# EGB220.net
KiCad netlist of a schematic drawn in Altium Designer
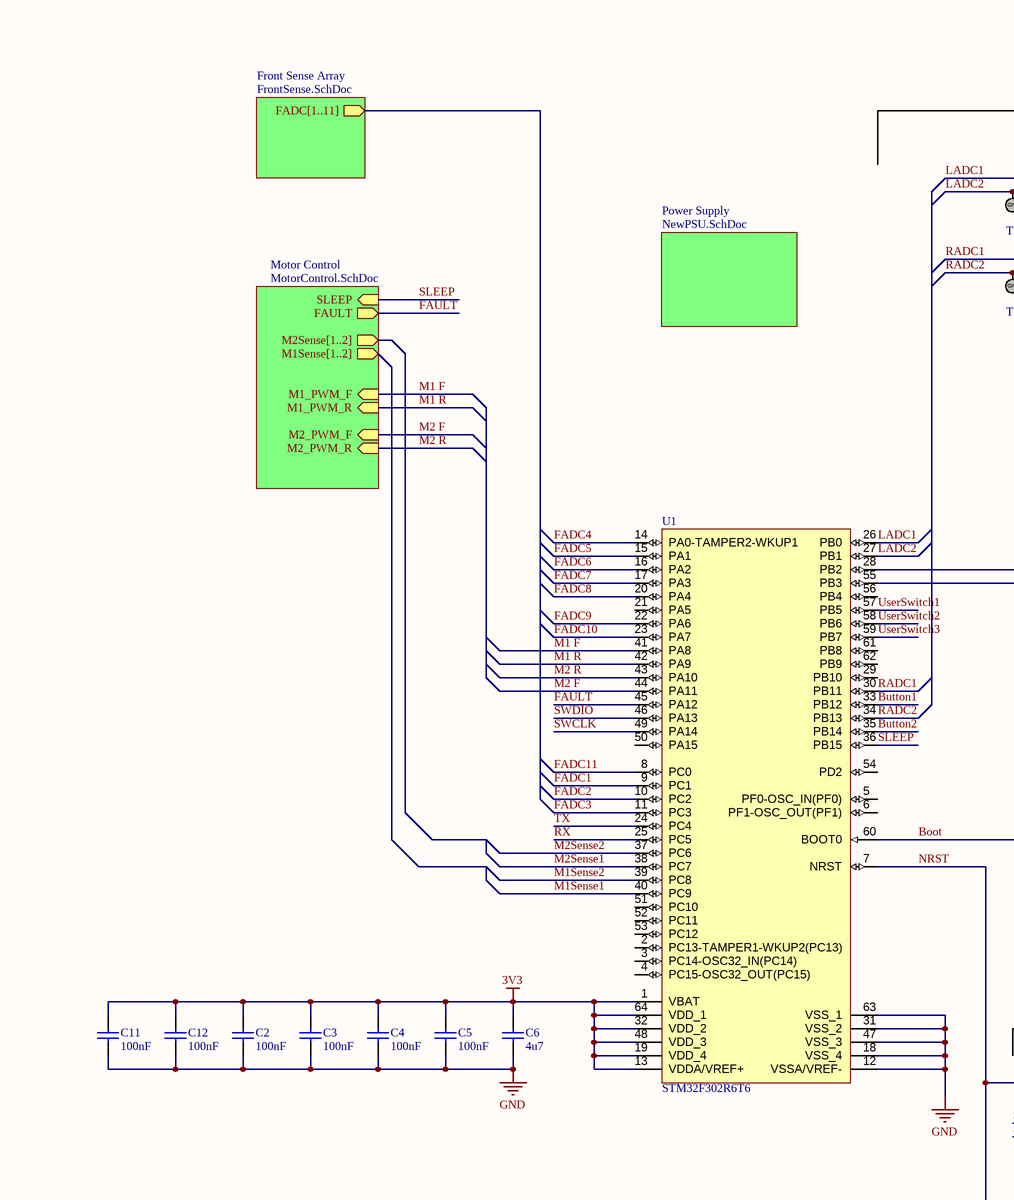
[diagram p0: EGB220.SchDoc, centre column 2 of 4]
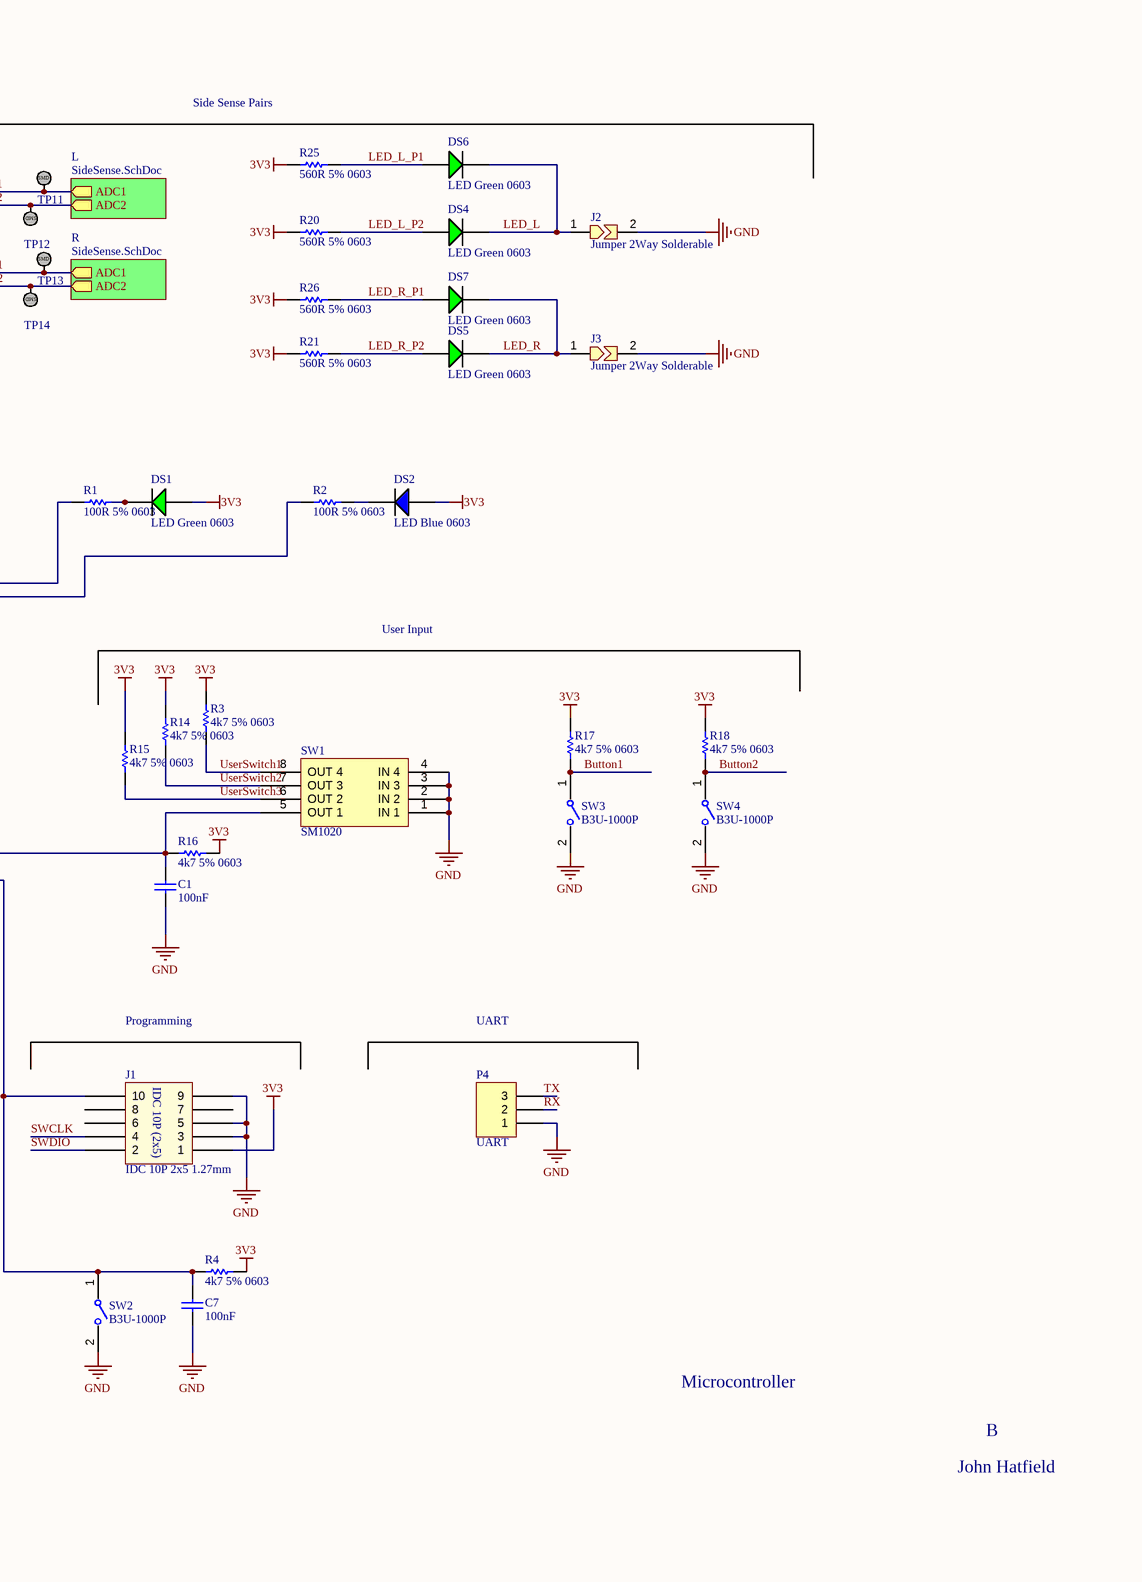
[diagram p1: EGB220.SchDoc, centre column 3 of 4]

(export (version "E")
  (design (tool "Eeschema 10.0.6"))
  (components
    (comp (ref "C1")
      (value "100nF")
      (footprint "Cap_Ceramic_0603")
      (description "Capacitor, Ceramic, SMD, 100nF, 50V, 5%, X7R, 0603")
      (libsource (lib "StandardCapacitors") (part "100nF 50V 5% X7R 0603"))
    )
    (comp (ref "C2")
      (value "100nF")
      (footprint "Cap_Ceramic_0603")
      (description "Capacitor, Ceramic, SMD, 100nF, 50V, 5%, X7R, 0603")
      (libsource (lib "StandardCapacitors") (part "100nF 50V 5% X7R 0603"))
    )
    (comp (ref "C3")
      (value "100nF")
      (footprint "Cap_Ceramic_0603")
      (description "Capacitor, Ceramic, SMD, 100nF, 50V, 5%, X7R, 0603")
      (libsource (lib "StandardCapacitors") (part "100nF 50V 5% X7R 0603"))
    )
    (comp (ref "C4")
      (value "100nF")
      (footprint "Cap_Ceramic_0603")
      (description "Capacitor, Ceramic, SMD, 100nF, 50V, 5%, X7R, 0603")
      (libsource (lib "StandardCapacitors") (part "100nF 50V 5% X7R 0603"))
    )
    (comp (ref "C5")
      (value "100nF")
      (footprint "Cap_Ceramic_0603")
      (description "Capacitor, Ceramic, SMD, 100nF, 50V, 5%, X7R, 0603")
      (libsource (lib "StandardCapacitors") (part "100nF 50V 5% X7R 0603"))
    )
    (comp (ref "C6")
      (value "4u7")
      (footprint "Cap_Ceramic_0603")
      (description "Capacitor, Ceramic, SMD, 4u7, 50V, 5%, X7R, 0603")
      (libsource (lib "StandardCapacitors") (part "4u7 50V 5% X7R 0603"))
    )
    (comp (ref "C7")
      (value "100nF")
      (footprint "Cap_Ceramic_0603")
      (description "Capacitor, Ceramic, SMD, 100nF, 50V, 5%, X7R, 0603")
      (libsource (lib "StandardCapacitors") (part "100nF 50V 5% X7R 0603"))
    )
    (comp (ref "C11")
      (value "100nF")
      (footprint "Cap_Ceramic_0603")
      (description "Capacitor, Ceramic, SMD, 100nF, 50V, 5%, X7R, 0603")
      (libsource (lib "StandardCapacitors") (part "100nF 50V 5% X7R 0603"))
    )
    (comp (ref "C12")
      (value "100nF")
      (footprint "Cap_Ceramic_0603")
      (description "Capacitor, Ceramic, SMD, 100nF, 50V, 5%, X7R, 0603")
      (libsource (lib "StandardCapacitors") (part "100nF 50V 5% X7R 0603"))
    )
    (comp (ref "DS1")
      (value "LED Green 0603")
      (footprint "LED GREEN 0603")
      (libsource (lib "QUTMS_LEDLibrary") (part "LED Green 0603"))
    )
    (comp (ref "DS2")
      (value "LED Blue 0603")
      (footprint "LED BLUE 0603")
      (libsource (lib "QUTMS_LEDLibrary") (part "LED Blue 0603"))
    )
    (comp (ref "DS4")
      (value "LED Green 0603")
      (footprint "LED GREEN 0603")
      (libsource (lib "QUTMS_LEDLibrary") (part "LED Green 0603"))
    )
    (comp (ref "DS5")
      (value "LED Green 0603")
      (footprint "LED GREEN 0603")
      (libsource (lib "QUTMS_LEDLibrary") (part "LED Green 0603"))
    )
    (comp (ref "DS6")
      (value "LED Green 0603")
      (footprint "LED GREEN 0603")
      (libsource (lib "QUTMS_LEDLibrary") (part "LED Green 0603"))
    )
    (comp (ref "DS7")
      (value "LED Green 0603")
      (footprint "LED GREEN 0603")
      (libsource (lib "QUTMS_LEDLibrary") (part "LED Green 0603"))
    )
    (comp (ref "J1")
      (value "IDC 10P 2x5 1.27mm")
      (footprint "IDC 1.27MM 10P")
      (libsource (lib "IDCConnectors") (part "IDC 10P 2x5 1.27mm"))
    )
    (comp (ref "J2")
      (value "Jumper 2Way Solderable")
      (footprint "Jumper_2Way_Solderable")
      (description "Jumper 2Way Vert Solderable")
      (libsource (lib "QUTMS_JumperLibrary") (part "Jumper 2Way Vert Solderable"))
    )
    (comp (ref "J3")
      (value "Jumper 2Way Solderable")
      (footprint "Jumper_2Way_Solderable")
      (description "Jumper 2Way Vert Solderable")
      (libsource (lib "QUTMS_JumperLibrary") (part "Jumper 2Way Vert Solderable"))
    )
    (comp (ref "P4")
      (value "UART")
      (footprint "HDR1X3")
      (description "Header, 3-Pin")
      (fields (field (name "PUBLISHER") "Altium Limited"))
      (libsource (lib "Miscellaneous Connectors") (part "Header 3"))
    )
    (comp (ref "R1")
      (value "100R 5% 0603")
      (footprint "Res_ThinFilm_0603")
      (description "Resistor, SMD, 100R, 0.1W, 5%, 0603")
      (libsource (lib "StandardResistors") (part "100R 5%, 0603"))
    )
    (comp (ref "R2")
      (value "100R 5% 0603")
      (footprint "Res_ThinFilm_0603")
      (description "Resistor, SMD, 100R, 0.1W, 5%, 0603")
      (libsource (lib "StandardResistors") (part "100R 5%, 0603"))
    )
    (comp (ref "R3")
      (value "4k7 5% 0603")
      (footprint "Res_ThinFilm_0603")
      (description "Resistor, SMD, 4k7, 0.1W, 5%, 0603")
      (libsource (lib "StandardResistors") (part "4k7 5% 0603"))
    )
    (comp (ref "R4")
      (value "4k7 5% 0603")
      (footprint "Res_ThinFilm_0603")
      (description "Resistor, SMD, 4k7, 0.1W, 5%, 0603")
      (libsource (lib "StandardResistors") (part "4k7 5% 0603"))
    )
    (comp (ref "R14")
      (value "4k7 5% 0603")
      (footprint "Res_ThinFilm_0603")
      (description "Resistor, SMD, 4k7, 0.1W, 5%, 0603")
      (libsource (lib "StandardResistors") (part "4k7 5% 0603"))
    )
    (comp (ref "R15")
      (value "4k7 5% 0603")
      (footprint "Res_ThinFilm_0603")
      (description "Resistor, SMD, 4k7, 0.1W, 5%, 0603")
      (libsource (lib "StandardResistors") (part "4k7 5% 0603"))
    )
    (comp (ref "R16")
      (value "4k7 5% 0603")
      (footprint "Res_ThinFilm_0603")
      (description "Resistor, SMD, 4k7, 0.1W, 5%, 0603")
      (libsource (lib "StandardResistors") (part "4k7 5% 0603"))
    )
    (comp (ref "R17")
      (value "4k7 5% 0603")
      (footprint "Res_ThinFilm_0603")
      (description "Resistor, SMD, 4k7, 0.1W, 5%, 0603")
      (libsource (lib "StandardResistors") (part "4k7 5% 0603"))
    )
    (comp (ref "R18")
      (value "4k7 5% 0603")
      (footprint "Res_ThinFilm_0603")
      (description "Resistor, SMD, 4k7, 0.1W, 5%, 0603")
      (libsource (lib "StandardResistors") (part "4k7 5% 0603"))
    )
    (comp (ref "R20")
      (value "560R 5% 0603")
      (footprint "Res_ThinFilm_0603")
      (description "Resistor, SMD, 560R, 0.1W, 5%, 0603")
      (libsource (lib "StandardResistors") (part "560R 5% 0603"))
    )
    (comp (ref "R21")
      (value "560R 5% 0603")
      (footprint "Res_ThinFilm_0603")
      (description "Resistor, SMD, 560R, 0.1W, 5%, 0603")
      (libsource (lib "StandardResistors") (part "560R 5% 0603"))
    )
    (comp (ref "R25")
      (value "560R 5% 0603")
      (footprint "Res_ThinFilm_0603")
      (description "Resistor, SMD, 560R, 0.1W, 5%, 0603")
      (libsource (lib "StandardResistors") (part "560R 5% 0603"))
    )
    (comp (ref "R26")
      (value "560R 5% 0603")
      (footprint "Res_ThinFilm_0603")
      (description "Resistor, SMD, 560R, 0.1W, 5%, 0603")
      (libsource (lib "StandardResistors") (part "560R 5% 0603"))
    )
    (comp (ref "SW1")
      (value "SM1020")
      (footprint "SM1020")
      (description "4 Pin DIL Switch")
      (libsource (lib "QUTMS_SwitchLibrary") (part "SM1020"))
    )
    (comp (ref "SW2")
      (value "B3U-1000P")
      (footprint "FP-B3U-1000P-MFG")
      (description "SWITCH TACTILE SPST-NO 0.05A 12V")
      (libsource (lib "Altium Content Vault") (part "ae622034201233ca1abcedc05908f33"))
    )
    (comp (ref "SW3")
      (value "B3U-1000P")
      (footprint "FP-B3U-1000P-MFG")
      (description "SWITCH TACTILE SPST-NO 0.05A 12V")
      (libsource (lib "Altium Content Vault") (part "ae622034201233ca1abcedc05908f33"))
    )
    (comp (ref "SW4")
      (value "B3U-1000P")
      (footprint "FP-B3U-1000P-MFG")
      (description "SWITCH TACTILE SPST-NO 0.05A 12V")
      (libsource (lib "Altium Content Vault") (part "ae622034201233ca1abcedc05908f33"))
    )
    (comp (ref "TP11")
      (value "TestPoint_SMD")
      (footprint "TestPointSMD")
      (libsource (lib "StandardTest") (part "TestPoint_SMD"))
    )
    (comp (ref "TP12")
      (value "TestPoint_SMD")
      (footprint "TestPointSMD")
      (libsource (lib "StandardTest") (part "TestPoint_SMD"))
    )
    (comp (ref "TP13")
      (value "TestPoint_SMD")
      (footprint "TestPointSMD")
      (libsource (lib "StandardTest") (part "TestPoint_SMD"))
    )
    (comp (ref "TP14")
      (value "TestPoint_SMD")
      (footprint "TestPointSMD")
      (libsource (lib "StandardTest") (part "TestPoint_SMD"))
    )
    (comp (ref "U1")
      (value "STM32F302R6T6")
      (footprint "STM-LQFP64_L")
      (libsource (lib "Altium Content Vault") (part "MC-ARM-STM32F30X-LQFP64"))
    )
  )
  (nets
    (net (code "1") (name "/Boot") (class "Default")
      (node (ref "C1") (pin "2") (pinfunction "2_2") (pintype "passive"))
      (node (ref "R16") (pin "2") (pinfunction "2_2") (pintype "passive"))
      (node (ref "SW1") (pin "5") (pinfunction "OUT_1_5") (pintype "passive"))
      (node (ref "U1") (pin "60") (pinfunction "BOOT0_60") (pintype "input"))
    )
    (net (code "2") (name "/Button1") (class "Default")
      (node (ref "R17") (pin "1") (pinfunction "1_1") (pintype "passive"))
      (node (ref "SW3") (pin "1") (pinfunction "1_1") (pintype "passive"))
      (node (ref "U1") (pin "33") (pinfunction "PB12_33") (pintype "bidirectional"))
    )
    (net (code "3") (name "/Button2") (class "Default")
      (node (ref "R18") (pin "1") (pinfunction "1_1") (pintype "passive"))
      (node (ref "SW4") (pin "1") (pinfunction "1_1") (pintype "passive"))
      (node (ref "U1") (pin "35") (pinfunction "PB14_35") (pintype "bidirectional"))
    )
    (net (code "4") (name "/FADC1") (class "Default")
      (node (ref "U1") (pin "9") (pinfunction "PC1_9") (pintype "bidirectional"))
    )
    (net (code "5") (name "/FADC2") (class "Default")
      (node (ref "U1") (pin "10") (pinfunction "PC2_10") (pintype "bidirectional"))
    )
    (net (code "6") (name "/FADC3") (class "Default")
      (node (ref "U1") (pin "11") (pinfunction "PC3_11") (pintype "bidirectional"))
    )
    (net (code "7") (name "/FADC4") (class "Default")
      (node (ref "U1") (pin "14") (pinfunction "PA0-TAMPER2-WKUP1_14") (pintype "bidirectional"))
    )
    (net (code "8") (name "/FADC5") (class "Default")
      (node (ref "U1") (pin "15") (pinfunction "PA1_15") (pintype "bidirectional"))
    )
    (net (code "9") (name "/FADC6") (class "Default")
      (node (ref "U1") (pin "16") (pinfunction "PA2_16") (pintype "bidirectional"))
    )
    (net (code "10") (name "/FADC7") (class "Default")
      (node (ref "U1") (pin "17") (pinfunction "PA3_17") (pintype "bidirectional"))
    )
    (net (code "11") (name "/FADC8") (class "Default")
      (node (ref "U1") (pin "20") (pinfunction "PA4_20") (pintype "bidirectional"))
    )
    (net (code "12") (name "/FADC9") (class "Default")
      (node (ref "U1") (pin "22") (pinfunction "PA6_22") (pintype "bidirectional"))
    )
    (net (code "13") (name "/FADC10") (class "Default")
      (node (ref "U1") (pin "23") (pinfunction "PA7_23") (pintype "bidirectional"))
    )
    (net (code "14") (name "/FADC11") (class "Default")
      (node (ref "U1") (pin "8") (pinfunction "PC0_8") (pintype "bidirectional"))
    )
    (net (code "16") (name "/FAULT") (class "Default")
      (node (ref "U1") (pin "45") (pinfunction "PA12_45") (pintype "bidirectional"))
    )
    (net (code "17") (name "/LADC1") (class "Default")
      (node (ref "TP11") (pin "1") (pinfunction "1_1") (pintype "passive"))
      (node (ref "U1") (pin "26") (pinfunction "PB0_26") (pintype "bidirectional"))
    )
    (net (code "18") (name "/LADC2") (class "Default")
      (node (ref "TP12") (pin "1") (pinfunction "1_1") (pintype "passive"))
      (node (ref "U1") (pin "27") (pinfunction "PB1_27") (pintype "bidirectional"))
    )
    (net (code "19") (name "/LED_L") (class "Default")
      (node (ref "DS4") (pin "2") (pinfunction "C_2") (pintype "passive"))
      (node (ref "DS6") (pin "2") (pinfunction "C_2") (pintype "passive"))
      (node (ref "J2") (pin "1") (pinfunction "1_1") (pintype "passive"))
    )
    (net (code "20") (name "/LED_L_P1") (class "Default")
      (node (ref "DS6") (pin "1") (pinfunction "A_1") (pintype "passive"))
      (node (ref "R25") (pin "1") (pinfunction "1_1") (pintype "passive"))
    )
    (net (code "21") (name "/LED_L_P2") (class "Default")
      (node (ref "DS4") (pin "1") (pinfunction "A_1") (pintype "passive"))
      (node (ref "R20") (pin "1") (pinfunction "1_1") (pintype "passive"))
    )
    (net (code "22") (name "/LED_R") (class "Default")
      (node (ref "DS5") (pin "2") (pinfunction "C_2") (pintype "passive"))
      (node (ref "DS7") (pin "2") (pinfunction "C_2") (pintype "passive"))
      (node (ref "J3") (pin "1") (pinfunction "1_1") (pintype "passive"))
    )
    (net (code "23") (name "/LED_R_P1") (class "Default")
      (node (ref "DS7") (pin "1") (pinfunction "A_1") (pintype "passive"))
      (node (ref "R26") (pin "1") (pinfunction "1_1") (pintype "passive"))
    )
    (net (code "24") (name "/LED_R_P2") (class "Default")
      (node (ref "DS5") (pin "1") (pinfunction "A_1") (pintype "passive"))
      (node (ref "R21") (pin "1") (pinfunction "1_1") (pintype "passive"))
    )
    (net (code "25") (name "/M1 F") (class "Default")
      (node (ref "U1") (pin "41") (pinfunction "PA8_41") (pintype "bidirectional"))
    )
    (net (code "26") (name "/M1 R") (class "Default")
      (node (ref "U1") (pin "42") (pinfunction "PA9_42") (pintype "bidirectional"))
    )
    (net (code "27") (name "/M1Sense1") (class "Default")
      (node (ref "U1") (pin "40") (pinfunction "PC9_40") (pintype "bidirectional"))
    )
    (net (code "28") (name "/M1Sense2") (class "Default")
      (node (ref "U1") (pin "39") (pinfunction "PC8_39") (pintype "bidirectional"))
    )
    (net (code "30") (name "/M2 F") (class "Default")
      (node (ref "U1") (pin "44") (pinfunction "PA11_44") (pintype "bidirectional"))
    )
    (net (code "31") (name "/M2 R") (class "Default")
      (node (ref "U1") (pin "43") (pinfunction "PA10_43") (pintype "bidirectional"))
    )
    (net (code "32") (name "/M2Sense1") (class "Default")
      (node (ref "U1") (pin "38") (pinfunction "PC7_38") (pintype "bidirectional"))
    )
    (net (code "33") (name "/M2Sense2") (class "Default")
      (node (ref "U1") (pin "37") (pinfunction "PC6_37") (pintype "bidirectional"))
    )
    (net (code "35") (name "/NRST") (class "Default")
      (node (ref "C7") (pin "2") (pinfunction "2_2") (pintype "passive"))
      (node (ref "J1") (pin "10") (pinfunction "10_10") (pintype "passive"))
      (node (ref "R4") (pin "2") (pinfunction "2_2") (pintype "passive"))
      (node (ref "SW2") (pin "1") (pinfunction "1_1") (pintype "passive"))
      (node (ref "U1") (pin "7") (pinfunction "NRST_7") (pintype "bidirectional"))
    )
    (net (code "36") (name "/RADC1") (class "Default")
      (node (ref "TP13") (pin "1") (pinfunction "1_1") (pintype "passive"))
      (node (ref "U1") (pin "30") (pinfunction "PB11_30") (pintype "bidirectional"))
    )
    (net (code "37") (name "/RADC2") (class "Default")
      (node (ref "TP14") (pin "1") (pinfunction "1_1") (pintype "passive"))
      (node (ref "U1") (pin "34") (pinfunction "PB13_34") (pintype "bidirectional"))
    )
    (net (code "38") (name "/RX") (class "Default")
      (node (ref "P4") (pin "2") (pinfunction "2_2") (pintype "passive"))
      (node (ref "U1") (pin "25") (pinfunction "PC5_25") (pintype "bidirectional"))
    )
    (net (code "39") (name "/SLEEP") (class "Default")
      (node (ref "U1") (pin "36") (pinfunction "PB15_36") (pintype "bidirectional"))
    )
    (net (code "40") (name "/SWCLK") (class "Default")
      (node (ref "J1") (pin "4") (pinfunction "4_4") (pintype "passive"))
      (node (ref "U1") (pin "49") (pinfunction "PA14_49") (pintype "bidirectional"))
    )
    (net (code "41") (name "/SWDIO") (class "Default")
      (node (ref "J1") (pin "2") (pinfunction "2_2") (pintype "passive"))
      (node (ref "U1") (pin "46") (pinfunction "PA13_46") (pintype "bidirectional"))
    )
    (net (code "42") (name "/TX") (class "Default")
      (node (ref "P4") (pin "3") (pinfunction "3_3") (pintype "passive"))
      (node (ref "U1") (pin "24") (pinfunction "PC4_24") (pintype "bidirectional"))
    )
    (net (code "43") (name "/UserSwitch1") (class "Default")
      (node (ref "R3") (pin "1") (pinfunction "1_1") (pintype "passive"))
      (node (ref "SW1") (pin "8") (pinfunction "OUT_4_8") (pintype "passive"))
      (node (ref "U1") (pin "57") (pinfunction "PB5_57") (pintype "bidirectional"))
    )
    (net (code "44") (name "/UserSwitch2") (class "Default")
      (node (ref "R14") (pin "1") (pinfunction "1_1") (pintype "passive"))
      (node (ref "SW1") (pin "7") (pinfunction "OUT_3_7") (pintype "passive"))
      (node (ref "U1") (pin "58") (pinfunction "PB6_58") (pintype "bidirectional"))
    )
    (net (code "45") (name "/UserSwitch3") (class "Default")
      (node (ref "R15") (pin "1") (pinfunction "1_1") (pintype "passive"))
      (node (ref "SW1") (pin "6") (pinfunction "OUT_2_6") (pintype "passive"))
      (node (ref "U1") (pin "59") (pinfunction "PB7_59") (pintype "bidirectional"))
    )
    (net (code "46") (name "3V3") (class "Default")
      (node (ref "C11") (pin "2") (pinfunction "2_2") (pintype "passive"))
      (node (ref "C12") (pin "2") (pinfunction "2_2") (pintype "passive"))
      (node (ref "C2") (pin "2") (pinfunction "2_2") (pintype "passive"))
      (node (ref "C3") (pin "2") (pinfunction "2_2") (pintype "passive"))
      (node (ref "C4") (pin "2") (pinfunction "2_2") (pintype "passive"))
      (node (ref "C5") (pin "2") (pinfunction "2_2") (pintype "passive"))
      (node (ref "C6") (pin "2") (pinfunction "2_2") (pintype "passive"))
      (node (ref "DS1") (pin "1") (pinfunction "A_1") (pintype "passive"))
      (node (ref "DS2") (pin "1") (pinfunction "A_1") (pintype "passive"))
      (node (ref "J1") (pin "1") (pinfunction "1_1") (pintype "passive"))
      (node (ref "R14") (pin "2") (pinfunction "2_2") (pintype "passive"))
      (node (ref "R15") (pin "2") (pinfunction "2_2") (pintype "passive"))
      (node (ref "R16") (pin "1") (pinfunction "1_1") (pintype "passive"))
      (node (ref "R17") (pin "2") (pinfunction "2_2") (pintype "passive"))
      (node (ref "R18") (pin "2") (pinfunction "2_2") (pintype "passive"))
      (node (ref "R20") (pin "2") (pinfunction "2_2") (pintype "passive"))
      (node (ref "R21") (pin "2") (pinfunction "2_2") (pintype "passive"))
      (node (ref "R25") (pin "2") (pinfunction "2_2") (pintype "passive"))
      (node (ref "R26") (pin "2") (pinfunction "2_2") (pintype "passive"))
      (node (ref "R3") (pin "2") (pinfunction "2_2") (pintype "passive"))
      (node (ref "R4") (pin "1") (pinfunction "1_1") (pintype "passive"))
      (node (ref "U1") (pin "1") (pinfunction "VBAT_1") (pintype "power_in"))
      (node (ref "U1") (pin "13") (pinfunction "VDDA/VREF+_13") (pintype "power_in"))
      (node (ref "U1") (pin "19") (pinfunction "VDD_4_19") (pintype "power_in"))
      (node (ref "U1") (pin "32") (pinfunction "VDD_2_32") (pintype "power_in"))
      (node (ref "U1") (pin "48") (pinfunction "VDD_3_48") (pintype "power_in"))
      (node (ref "U1") (pin "64") (pinfunction "VDD_1_64") (pintype "power_in"))
    )
    (net (code "47") (name "GND") (class "Default")
      (node (ref "C1") (pin "1") (pinfunction "1_1") (pintype "passive"))
      (node (ref "C11") (pin "1") (pinfunction "1_1") (pintype "passive"))
      (node (ref "C12") (pin "1") (pinfunction "1_1") (pintype "passive"))
      (node (ref "C2") (pin "1") (pinfunction "1_1") (pintype "passive"))
      (node (ref "C3") (pin "1") (pinfunction "1_1") (pintype "passive"))
      (node (ref "C4") (pin "1") (pinfunction "1_1") (pintype "passive"))
      (node (ref "C5") (pin "1") (pinfunction "1_1") (pintype "passive"))
      (node (ref "C6") (pin "1") (pinfunction "1_1") (pintype "passive"))
      (node (ref "C7") (pin "1") (pinfunction "1_1") (pintype "passive"))
      (node (ref "J1") (pin "3") (pinfunction "3_3") (pintype "passive"))
      (node (ref "J1") (pin "5") (pinfunction "5_5") (pintype "passive"))
      (node (ref "J1") (pin "9") (pinfunction "9_9") (pintype "passive"))
      (node (ref "J2") (pin "2") (pinfunction "2_2") (pintype "passive"))
      (node (ref "J3") (pin "2") (pinfunction "2_2") (pintype "passive"))
      (node (ref "P4") (pin "1") (pinfunction "1_1") (pintype "passive"))
      (node (ref "SW1") (pin "1") (pinfunction "IN_1_1") (pintype "passive"))
      (node (ref "SW1") (pin "2") (pinfunction "IN_2_2") (pintype "passive"))
      (node (ref "SW1") (pin "3") (pinfunction "IN_3_3") (pintype "passive"))
      (node (ref "SW1") (pin "4") (pinfunction "IN_4_4") (pintype "passive"))
      (node (ref "SW2") (pin "2") (pinfunction "2_2") (pintype "passive"))
      (node (ref "SW3") (pin "2") (pinfunction "2_2") (pintype "passive"))
      (node (ref "SW4") (pin "2") (pinfunction "2_2") (pintype "passive"))
      (node (ref "U1") (pin "12") (pinfunction "VSSA/VREF-_12") (pintype "power_in"))
      (node (ref "U1") (pin "18") (pinfunction "VSS_4_18") (pintype "power_in"))
      (node (ref "U1") (pin "31") (pinfunction "VSS_2_31") (pintype "power_in"))
      (node (ref "U1") (pin "47") (pinfunction "VSS_3_47") (pintype "power_in"))
      (node (ref "U1") (pin "63") (pinfunction "VSS_1_63") (pintype "power_in"))
    )
    (net (code "48") (name "Net-(DS1-C)") (class "Default")
      (node (ref "DS1") (pin "2") (pinfunction "C_2") (pintype "passive"))
      (node (ref "R1") (pin "2") (pinfunction "2_2") (pintype "passive"))
    )
    (net (code "49") (name "Net-(DS2-C)") (class "Default")
      (node (ref "DS2") (pin "2") (pinfunction "C_2") (pintype "passive"))
      (node (ref "R2") (pin "2") (pinfunction "2_2") (pintype "passive"))
    )
    (net (code "50") (name "Net-(U1-PB2)") (class "Default")
      (node (ref "R1") (pin "1") (pinfunction "1_1") (pintype "passive"))
      (node (ref "U1") (pin "28") (pinfunction "PB2_28") (pintype "bidirectional"))
    )
    (net (code "51") (name "Net-(U1-PB3)") (class "Default")
      (node (ref "R2") (pin "1") (pinfunction "1_1") (pintype "passive"))
      (node (ref "U1") (pin "55") (pinfunction "PB3_55") (pintype "bidirectional"))
    )
    (net (code "52") (name "unconnected-(J1-Pad6)") (class "Default")
      (node (ref "J1") (pin "6") (pinfunction "6_6") (pintype "passive"))
    )
    (net (code "53") (name "unconnected-(J1-Pad7)") (class "Default")
      (node (ref "J1") (pin "7") (pinfunction "7_7") (pintype "passive"))
    )
    (net (code "54") (name "unconnected-(J1-Pad8)") (class "Default")
      (node (ref "J1") (pin "8") (pinfunction "8_8") (pintype "passive"))
    )
    (net (code "55") (name "unconnected-(U1-PA5-Pad21)") (class "Default")
      (node (ref "U1") (pin "21") (pinfunction "PA5_21") (pintype "bidirectional"))
    )
    (net (code "56") (name "unconnected-(U1-PA15-Pad50)") (class "Default")
      (node (ref "U1") (pin "50") (pinfunction "PA15_50") (pintype "bidirectional"))
    )
    (net (code "57") (name "unconnected-(U1-PB4-Pad56)") (class "Default")
      (node (ref "U1") (pin "56") (pinfunction "PB4_56") (pintype "bidirectional"))
    )
    (net (code "58") (name "unconnected-(U1-PB8-Pad61)") (class "Default")
      (node (ref "U1") (pin "61") (pinfunction "PB8_61") (pintype "bidirectional"))
    )
    (net (code "59") (name "unconnected-(U1-PB9-Pad62)") (class "Default")
      (node (ref "U1") (pin "62") (pinfunction "PB9_62") (pintype "bidirectional"))
    )
    (net (code "60") (name "unconnected-(U1-PB10-Pad29)") (class "Default")
      (node (ref "U1") (pin "29") (pinfunction "PB10_29") (pintype "bidirectional"))
    )
    (net (code "61") (name "unconnected-(U1-PC10-Pad51)") (class "Default")
      (node (ref "U1") (pin "51") (pinfunction "PC10_51") (pintype "bidirectional"))
    )
    (net (code "62") (name "unconnected-(U1-PC11-Pad52)") (class "Default")
      (node (ref "U1") (pin "52") (pinfunction "PC11_52") (pintype "bidirectional"))
    )
    (net (code "63") (name "unconnected-(U1-PC12-Pad53)") (class "Default")
      (node (ref "U1") (pin "53") (pinfunction "PC12_53") (pintype "bidirectional"))
    )
    (net (code "64") (name "unconnected-(U1-PC13-TAMPER1-WKUP2(PC13)-Pad2)") (class "Default")
      (node (ref "U1") (pin "2") (pinfunction "PC13-TAMPER1-WKUP2(PC13)_2") (pintype "bidirectional"))
    )
    (net (code "65") (name "unconnected-(U1-PC14-OSC32_IN(PC14)-Pad3)") (class "Default")
      (node (ref "U1") (pin "3") (pinfunction "PC14-OSC32_IN(PC14)_3") (pintype "bidirectional"))
    )
    (net (code "66") (name "unconnected-(U1-PC15-OSC32_OUT(PC15)-Pad4)") (class "Default")
      (node (ref "U1") (pin "4") (pinfunction "PC15-OSC32_OUT(PC15)_4") (pintype "bidirectional"))
    )
    (net (code "67") (name "unconnected-(U1-PD2-Pad54)") (class "Default")
      (node (ref "U1") (pin "54") (pinfunction "PD2_54") (pintype "bidirectional"))
    )
    (net (code "68") (name "unconnected-(U1-PF0-OSC_IN(PF0)-Pad5)") (class "Default")
      (node (ref "U1") (pin "5") (pinfunction "PF0-OSC_IN(PF0)_5") (pintype "bidirectional"))
    )
    (net (code "69") (name "unconnected-(U1-PF1-OSC_OUT(PF1)-Pad6)") (class "Default")
      (node (ref "U1") (pin "6") (pinfunction "PF1-OSC_OUT(PF1)_6") (pintype "bidirectional"))
    )
  )
)
